# XEPHITS.net
KiCad netlist of a schematic drawn in EAGLE
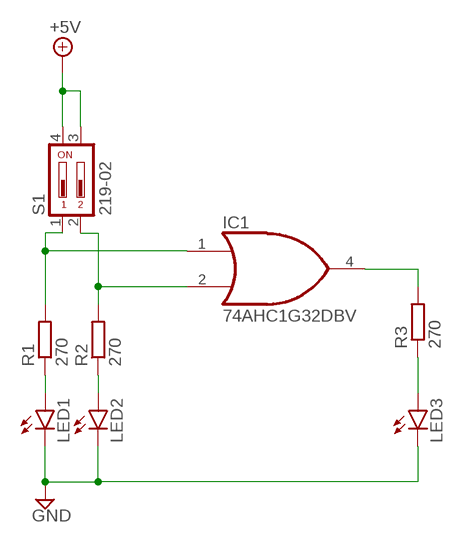
[diagram p0: schematic, sheet 1]

(export (version "E")
  (design (tool "Eeschema 10.0.6"))
  (components
    (comp (ref "IC1")
      (value "74AHC1G32DBV")
      (footprint "eagle-import:SOT23-5")
      (libsource (lib "eagle-import") (part "741G32DBVAHC"))
    )
    (comp (ref "LED1")
      (value "LAP4-BOTTOM")
      (footprint "eagle-import:P47F-BOTTOM")
      (libsource (lib "eagle-import") (part "P4-BOTTOMLA"))
    )
    (comp (ref "LED2")
      (value "LAP4-BOTTOM")
      (footprint "eagle-import:P47F-BOTTOM")
      (libsource (lib "eagle-import") (part "P4-BOTTOMLA"))
    )
    (comp (ref "LED3")
      (value "LAP4-BOTTOM")
      (footprint "eagle-import:P47F-BOTTOM")
      (libsource (lib "eagle-import") (part "P4-BOTTOMLA"))
    )
    (comp (ref "R1")
      (value "270")
      (footprint "eagle-import:0207_2V")
      (libsource (lib "eagle-import") (part "R-EU_0207/2V"))
    )
    (comp (ref "R2")
      (value "270")
      (footprint "eagle-import:0207_2V")
      (libsource (lib "eagle-import") (part "R-EU_0207/2V"))
    )
    (comp (ref "R3")
      (value "270")
      (footprint "eagle-import:0207_2V")
      (libsource (lib "eagle-import") (part "R-EU_0207/2V"))
    )
    (comp (ref "S1")
      (value "219-02")
      (footprint "eagle-import:CTS-219-02")
      (libsource (lib "eagle-import") (part "219-02"))
    )
  )
  (nets
    (net (code "1") (name "+5V") (class "Default")
      (node (ref "S1") (pin "3") (pinfunction "3_3") (pintype "passive"))
      (node (ref "S1") (pin "4") (pinfunction "4_4") (pintype "passive"))
    )
    (net (code "2") (name "GND") (class "Default")
      (node (ref "LED1") (pin "C") (pinfunction "C_C") (pintype "passive"))
      (node (ref "LED2") (pin "C") (pinfunction "C_C") (pintype "passive"))
      (node (ref "LED3") (pin "C") (pinfunction "C_C") (pintype "passive"))
    )
    (net (code "3") (name "Net-(IC1A-I0)") (class "Default")
      (node (ref "IC1") (pin "1") (pinfunction "I0_1") (pintype "input"))
      (node (ref "R1") (pin "2") (pinfunction "2_2") (pintype "passive"))
      (node (ref "S1") (pin "1") (pinfunction "1_1") (pintype "passive"))
    )
    (net (code "4") (name "Net-(IC1A-I1)") (class "Default")
      (node (ref "IC1") (pin "2") (pinfunction "I1_2") (pintype "input"))
      (node (ref "R2") (pin "2") (pinfunction "2_2") (pintype "passive"))
      (node (ref "S1") (pin "2") (pinfunction "2_2") (pintype "passive"))
    )
    (net (code "5") (name "Net-(IC1A-O)") (class "Default")
      (node (ref "IC1") (pin "4") (pinfunction "O_4") (pintype "output"))
      (node (ref "R3") (pin "2") (pinfunction "2_2") (pintype "passive"))
    )
    (net (code "6") (name "Net-(LED1-PadA)") (class "Default")
      (node (ref "LED1") (pin "A") (pinfunction "A_A") (pintype "passive"))
      (node (ref "R1") (pin "1") (pinfunction "1_1") (pintype "passive"))
    )
    (net (code "7") (name "Net-(LED2-PadA)") (class "Default")
      (node (ref "LED2") (pin "A") (pinfunction "A_A") (pintype "passive"))
      (node (ref "R2") (pin "1") (pinfunction "1_1") (pintype "passive"))
    )
    (net (code "8") (name "Net-(LED3-PadA)") (class "Default")
      (node (ref "LED3") (pin "A") (pinfunction "A_A") (pintype "passive"))
      (node (ref "R3") (pin "1") (pinfunction "1_1") (pintype "passive"))
    )
  )
)
